# Hi-Hat.net
KiCad netlist of a schematic drawn in EAGLE
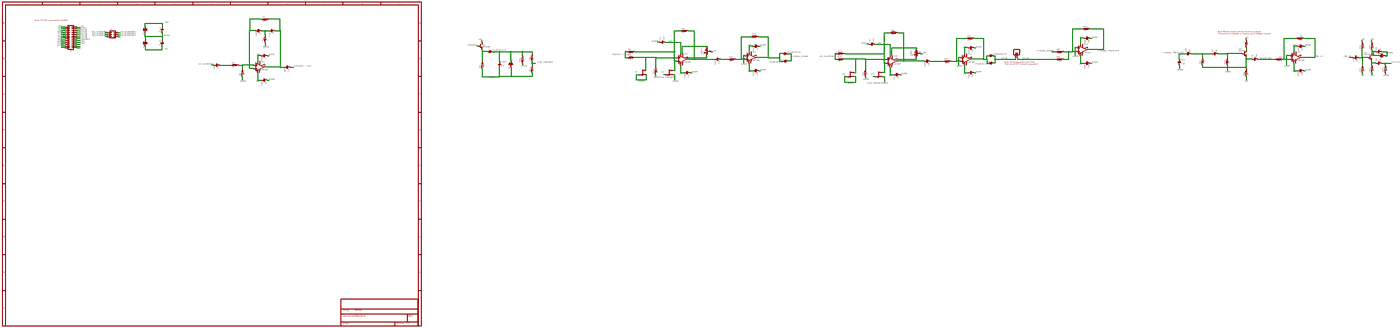
[diagram p0: schematic, sheet 1, overview]
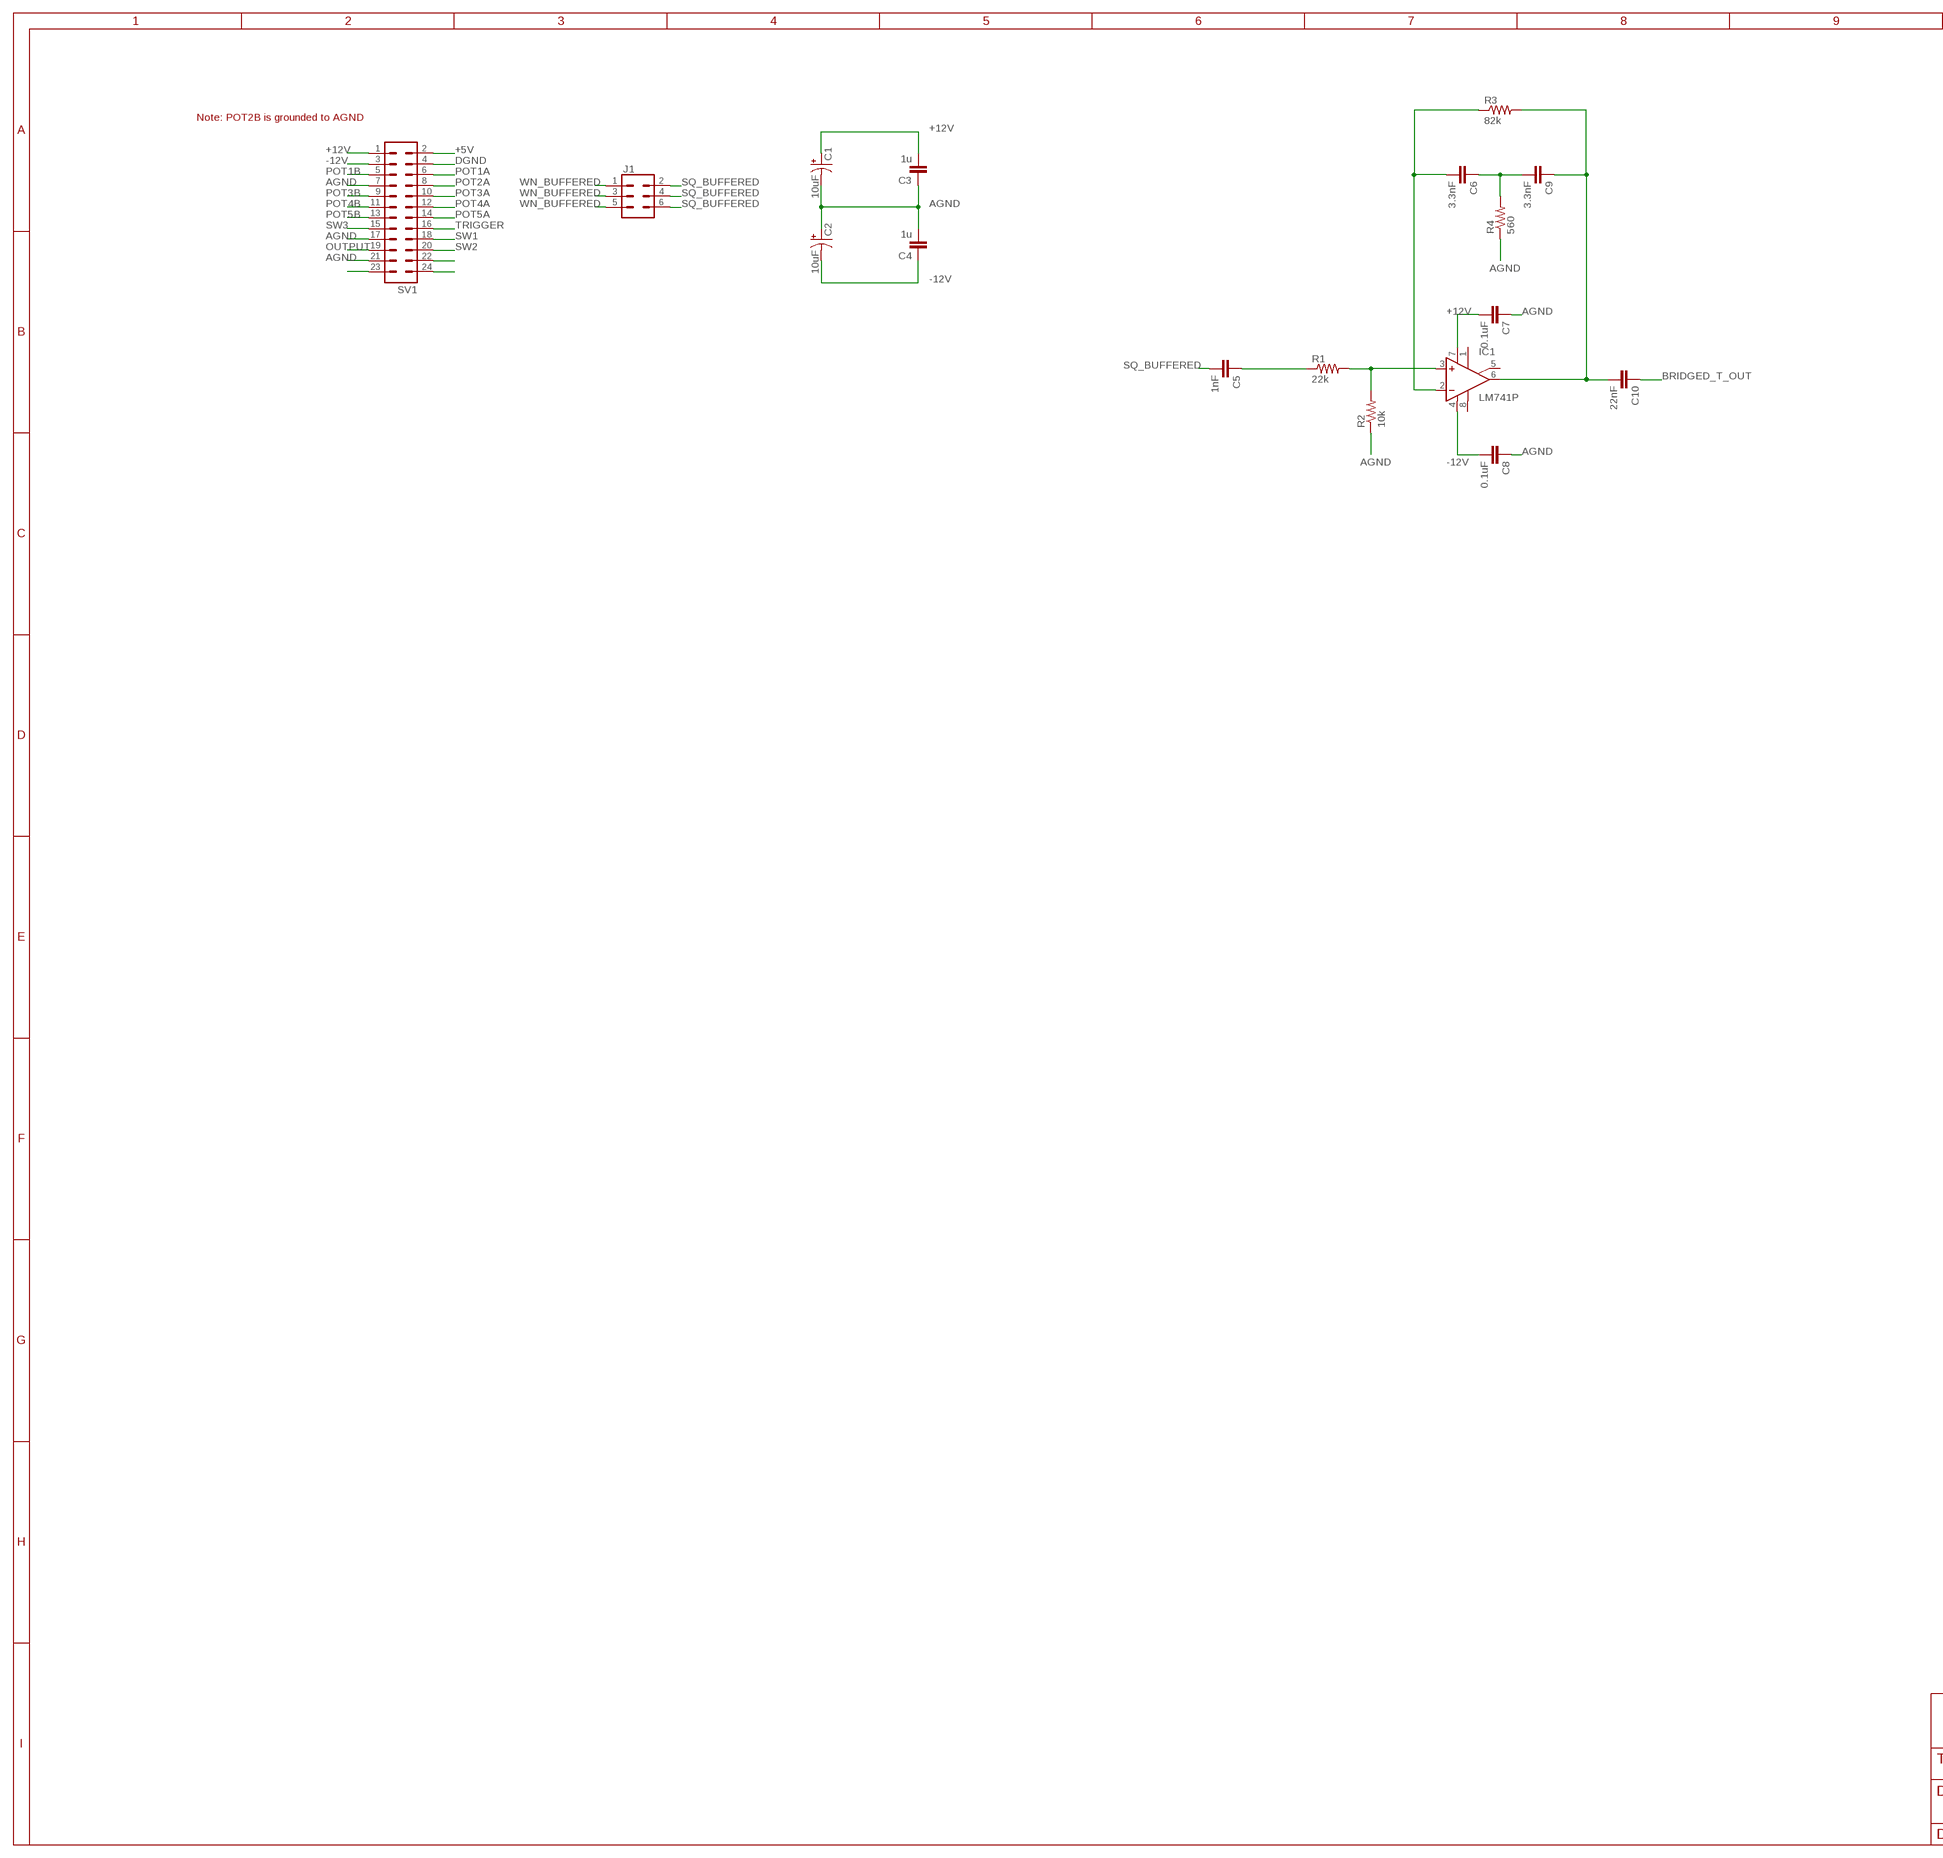
[diagram p1: schematic, sheet 1, part 1 of 4]
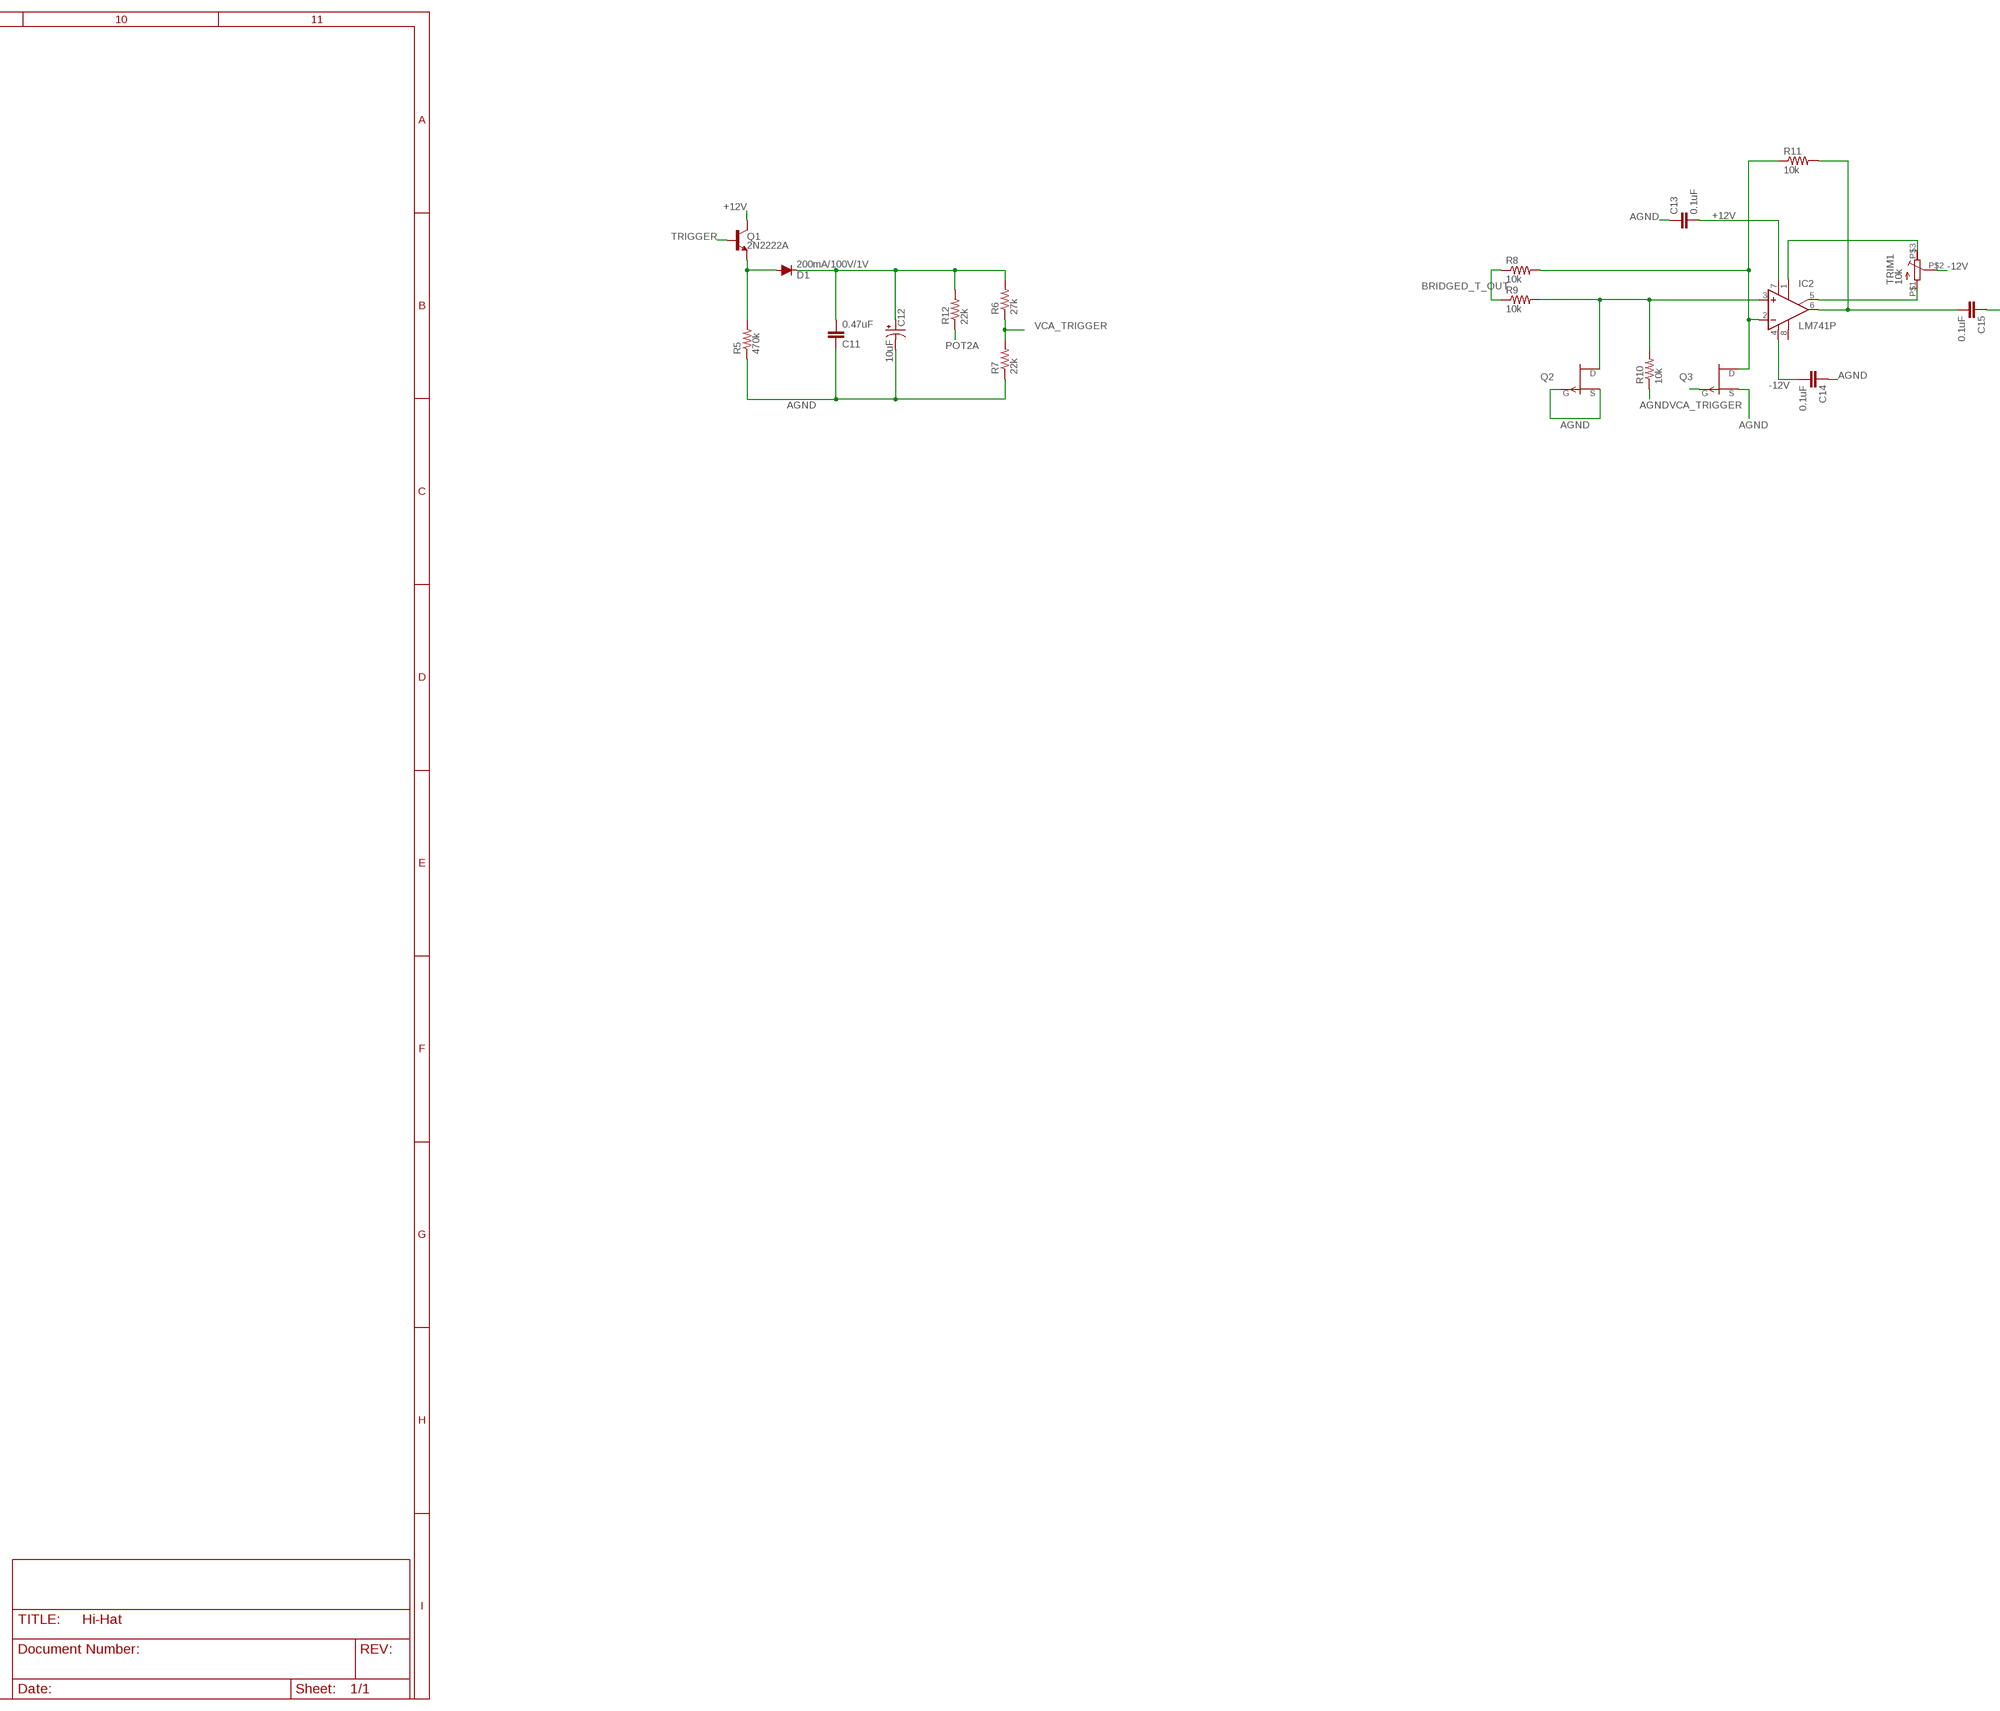
[diagram p2: schematic, sheet 1, part 2 of 4]
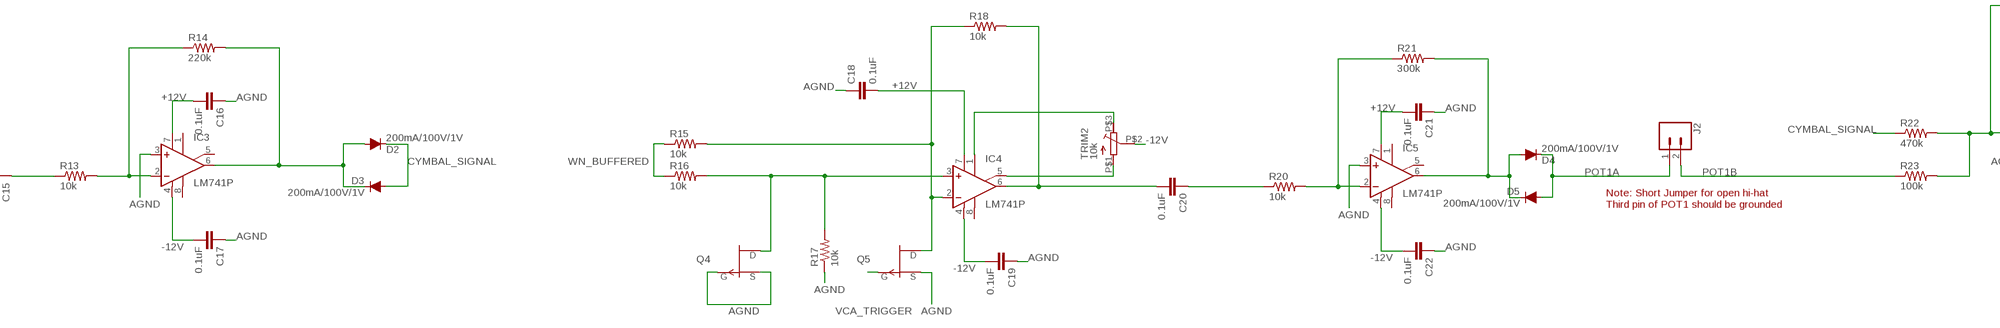
[diagram p3: schematic, sheet 1, part 3 of 4]
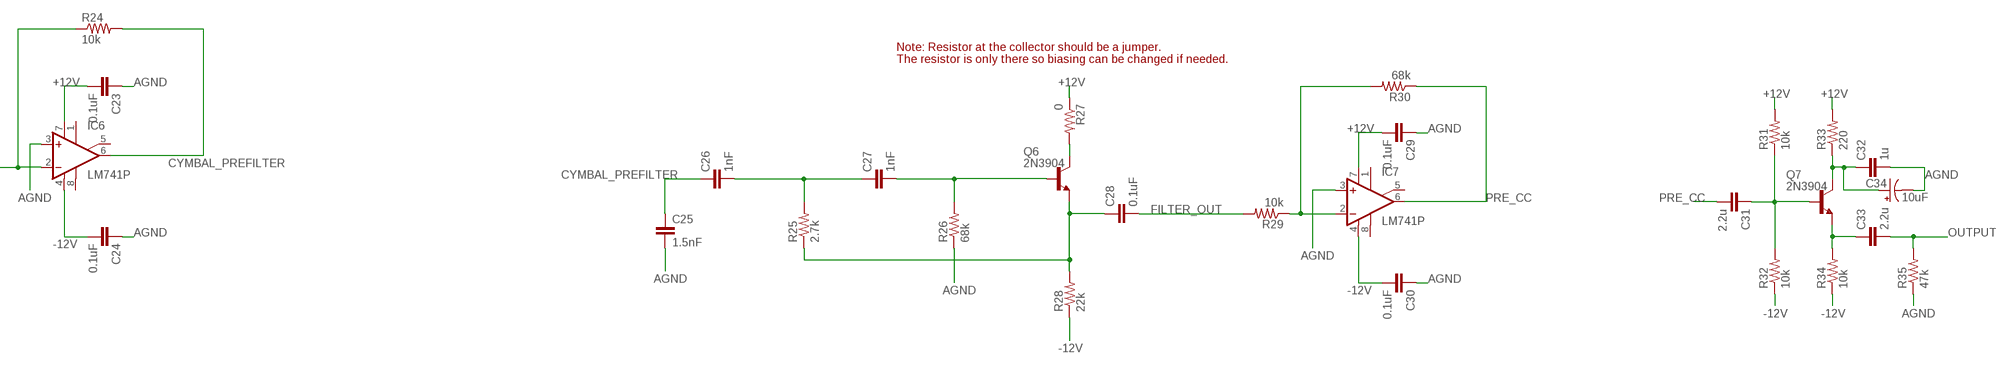
[diagram p4: schematic, sheet 1, part 4 of 4]

(export (version "E")
  (design (tool "Eeschema 10.0.6"))
  (components
    (comp (ref "C1")
      (value "10uF")
      (footprint "eagle-import:E2,5-6")
      (libsource (lib "eagle-import") (part "CPOL-USE2.5-6"))
    )
    (comp (ref "C2")
      (value "10uF")
      (footprint "eagle-import:E2,5-6")
      (libsource (lib "eagle-import") (part "CPOL-USE2.5-6"))
    )
    (comp (ref "C3")
      (value "1u")
      (footprint "eagle-import:C050-024X044")
      (libsource (lib "eagle-import") (part "C-EU050-024X044"))
    )
    (comp (ref "C4")
      (value "1u")
      (footprint "eagle-import:C050-024X044")
      (libsource (lib "eagle-import") (part "C-EU050-024X044"))
    )
    (comp (ref "C5")
      (value "1nF")
      (footprint "eagle-import:C050-024X044")
      (libsource (lib "eagle-import") (part "C-EU050-024X044"))
    )
    (comp (ref "C6")
      (value "3.3nF")
      (footprint "eagle-import:C050-024X044")
      (libsource (lib "eagle-import") (part "C-EU050-024X044"))
    )
    (comp (ref "C7")
      (value "0.1uF")
      (footprint "eagle-import:C050-024X044")
      (libsource (lib "eagle-import") (part "C-EU050-024X044"))
    )
    (comp (ref "C8")
      (value "0.1uF")
      (footprint "eagle-import:C050-024X044")
      (libsource (lib "eagle-import") (part "C-EU050-024X044"))
    )
    (comp (ref "C9")
      (value "3.3nF")
      (footprint "eagle-import:C050-024X044")
      (libsource (lib "eagle-import") (part "C-EU050-024X044"))
    )
    (comp (ref "C10")
      (value "22nF")
      (footprint "eagle-import:C050-024X044")
      (libsource (lib "eagle-import") (part "C-EU050-024X044"))
    )
    (comp (ref "C11")
      (value "0.47uF")
      (footprint "eagle-import:C050-024X044")
      (libsource (lib "eagle-import") (part "C-EU050-024X044"))
    )
    (comp (ref "C12")
      (value "10uF")
      (footprint "eagle-import:E2,5-6")
      (libsource (lib "eagle-import") (part "CPOL-USE2.5-6"))
    )
    (comp (ref "C13")
      (value "0.1uF")
      (footprint "eagle-import:C050-024X044")
      (libsource (lib "eagle-import") (part "C-EU050-024X044"))
    )
    (comp (ref "C14")
      (value "0.1uF")
      (footprint "eagle-import:C050-024X044")
      (libsource (lib "eagle-import") (part "C-EU050-024X044"))
    )
    (comp (ref "C15")
      (value "0.1uF")
      (footprint "eagle-import:C050-024X044")
      (libsource (lib "eagle-import") (part "C-EU050-024X044"))
    )
    (comp (ref "C16")
      (value "0.1uF")
      (footprint "eagle-import:C050-024X044")
      (libsource (lib "eagle-import") (part "C-EU050-024X044"))
    )
    (comp (ref "C17")
      (value "0.1uF")
      (footprint "eagle-import:C050-024X044")
      (libsource (lib "eagle-import") (part "C-EU050-024X044"))
    )
    (comp (ref "C18")
      (value "0.1uF")
      (footprint "eagle-import:C050-024X044")
      (libsource (lib "eagle-import") (part "C-EU050-024X044"))
    )
    (comp (ref "C19")
      (value "0.1uF")
      (footprint "eagle-import:C050-024X044")
      (libsource (lib "eagle-import") (part "C-EU050-024X044"))
    )
    (comp (ref "C20")
      (value "0.1uF")
      (footprint "eagle-import:C050-024X044")
      (libsource (lib "eagle-import") (part "C-EU050-024X044"))
    )
    (comp (ref "C21")
      (value "0.1uF")
      (footprint "eagle-import:C050-024X044")
      (libsource (lib "eagle-import") (part "C-EU050-024X044"))
    )
    (comp (ref "C22")
      (value "0.1uF")
      (footprint "eagle-import:C050-024X044")
      (libsource (lib "eagle-import") (part "C-EU050-024X044"))
    )
    (comp (ref "C23")
      (value "0.1uF")
      (footprint "eagle-import:C050-024X044")
      (libsource (lib "eagle-import") (part "C-EU050-024X044"))
    )
    (comp (ref "C24")
      (value "0.1uF")
      (footprint "eagle-import:C050-024X044")
      (libsource (lib "eagle-import") (part "C-EU050-024X044"))
    )
    (comp (ref "C25")
      (value "1.5nF")
      (footprint "eagle-import:C050-024X044")
      (libsource (lib "eagle-import") (part "C-EU050-024X044"))
    )
    (comp (ref "C26")
      (value "1nF")
      (footprint "eagle-import:C050-024X044")
      (libsource (lib "eagle-import") (part "C-EU050-024X044"))
    )
    (comp (ref "C27")
      (value "1nF")
      (footprint "eagle-import:C050-024X044")
      (libsource (lib "eagle-import") (part "C-EU050-024X044"))
    )
    (comp (ref "C28")
      (value "0.1uF")
      (footprint "eagle-import:C050-024X044")
      (libsource (lib "eagle-import") (part "C-EU050-024X044"))
    )
    (comp (ref "C29")
      (value "0.1uF")
      (footprint "eagle-import:C050-024X044")
      (libsource (lib "eagle-import") (part "C-EU050-024X044"))
    )
    (comp (ref "C30")
      (value "0.1uF")
      (footprint "eagle-import:C050-024X044")
      (libsource (lib "eagle-import") (part "C-EU050-024X044"))
    )
    (comp (ref "C31")
      (value "2.2u")
      (footprint "eagle-import:C050-024X044")
      (libsource (lib "eagle-import") (part "C-EU050-024X044"))
    )
    (comp (ref "C32")
      (value "1u")
      (footprint "eagle-import:C050-024X044")
      (libsource (lib "eagle-import") (part "C-EU050-024X044"))
    )
    (comp (ref "C33")
      (value "2.2u")
      (footprint "eagle-import:C050-024X044")
      (libsource (lib "eagle-import") (part "C-EU050-024X044"))
    )
    (comp (ref "C34")
      (value "10uF")
      (footprint "eagle-import:E2,5-6")
      (libsource (lib "eagle-import") (part "CPOL-USE2.5-6"))
    )
    (comp (ref "D1")
      (value "200mA/100V/1V")
      (footprint "eagle-import:DIODE-1N4148")
      (libsource (lib "eagle-import") (part "DIODE-1N4148"))
    )
    (comp (ref "D2")
      (value "200mA/100V/1V")
      (footprint "eagle-import:DIODE-1N4148")
      (libsource (lib "eagle-import") (part "DIODE-1N4148"))
    )
    (comp (ref "D3")
      (value "200mA/100V/1V")
      (footprint "eagle-import:DIODE-1N4148")
      (libsource (lib "eagle-import") (part "DIODE-1N4148"))
    )
    (comp (ref "D4")
      (value "200mA/100V/1V")
      (footprint "eagle-import:DIODE-1N4148")
      (libsource (lib "eagle-import") (part "DIODE-1N4148"))
    )
    (comp (ref "D5")
      (value "200mA/100V/1V")
      (footprint "eagle-import:DIODE-1N4148")
      (libsource (lib "eagle-import") (part "DIODE-1N4148"))
    )
    (comp (ref "IC1")
      (value "LM741P")
      (footprint "eagle-import:DIL08")
      (libsource (lib "eagle-import") (part "741PLM"))
    )
    (comp (ref "IC2")
      (value "LM741P")
      (footprint "eagle-import:DIL08")
      (libsource (lib "eagle-import") (part "741PLM"))
    )
    (comp (ref "IC3")
      (value "LM741P")
      (footprint "eagle-import:DIL08")
      (libsource (lib "eagle-import") (part "741PLM"))
    )
    (comp (ref "IC4")
      (value "LM741P")
      (footprint "eagle-import:DIL08")
      (libsource (lib "eagle-import") (part "741PLM"))
    )
    (comp (ref "IC5")
      (value "LM741P")
      (footprint "eagle-import:DIL08")
      (libsource (lib "eagle-import") (part "741PLM"))
    )
    (comp (ref "IC6")
      (value "LM741P")
      (footprint "eagle-import:DIL08")
      (libsource (lib "eagle-import") (part "741PLM"))
    )
    (comp (ref "IC7")
      (value "LM741P")
      (footprint "eagle-import:DIL08")
      (libsource (lib "eagle-import") (part "741PLM"))
    )
    (comp (ref "J1")
      (value "CONN_03X2NO_SILK")
      (footprint "eagle-import:2X3-NS")
      (libsource (lib "eagle-import") (part "CONN_03X2NO_SILK"))
    )
    (comp (ref "J2")
      (value "CONN_02")
      (footprint "eagle-import:1X02")
      (libsource (lib "eagle-import") (part "CONN_02"))
    )
    (comp (ref "Q1")
      (value "2N2222A")
      (footprint "eagle-import:TO-92")
      (libsource (lib "eagle-import") (part "TRANS_NPN-P2N2222A"))
    )
    (comp (ref "Q2")
      (value "J176")
      (footprint "eagle-import:TO-92")
      (libsource (lib "eagle-import") (part "J176"))
    )
    (comp (ref "Q3")
      (value "J176")
      (footprint "eagle-import:TO-92")
      (libsource (lib "eagle-import") (part "J176"))
    )
    (comp (ref "Q4")
      (value "J176")
      (footprint "eagle-import:TO-92")
      (libsource (lib "eagle-import") (part "J176"))
    )
    (comp (ref "Q5")
      (value "J176")
      (footprint "eagle-import:TO-92")
      (libsource (lib "eagle-import") (part "J176"))
    )
    (comp (ref "Q6")
      (value "2N3904")
      (footprint "eagle-import:TO92")
      (libsource (lib "eagle-import") (part "2N3904"))
    )
    (comp (ref "Q7")
      (value "2N3904")
      (footprint "eagle-import:TO92")
      (libsource (lib "eagle-import") (part "2N3904"))
    )
    (comp (ref "R1")
      (value "22k")
      (footprint "eagle-import:0207_7")
      (libsource (lib "eagle-import") (part "R-US_0207/7"))
    )
    (comp (ref "R2")
      (value "10k")
      (footprint "eagle-import:0207_7")
      (libsource (lib "eagle-import") (part "R-US_0207/7"))
    )
    (comp (ref "R3")
      (value "82k")
      (footprint "eagle-import:0207_7")
      (libsource (lib "eagle-import") (part "R-US_0207/7"))
    )
    (comp (ref "R4")
      (value "560")
      (footprint "eagle-import:0207_7")
      (libsource (lib "eagle-import") (part "R-US_0207/7"))
    )
    (comp (ref "R5")
      (value "470k")
      (footprint "eagle-import:0207_7")
      (libsource (lib "eagle-import") (part "R-US_0207/7"))
    )
    (comp (ref "R6")
      (value "27k")
      (footprint "eagle-import:0207_7")
      (libsource (lib "eagle-import") (part "R-US_0207/7"))
    )
    (comp (ref "R7")
      (value "22k")
      (footprint "eagle-import:0207_7")
      (libsource (lib "eagle-import") (part "R-US_0207/7"))
    )
    (comp (ref "R8")
      (value "10k")
      (footprint "eagle-import:0207_7")
      (libsource (lib "eagle-import") (part "R-US_0207/7"))
    )
    (comp (ref "R9")
      (value "10k")
      (footprint "eagle-import:0207_7")
      (libsource (lib "eagle-import") (part "R-US_0207/7"))
    )
    (comp (ref "R10")
      (value "10k")
      (footprint "eagle-import:0207_7")
      (libsource (lib "eagle-import") (part "R-US_0207/7"))
    )
    (comp (ref "R11")
      (value "10k")
      (footprint "eagle-import:0207_7")
      (libsource (lib "eagle-import") (part "R-US_0207/7"))
    )
    (comp (ref "R12")
      (value "22k")
      (footprint "eagle-import:0207_7")
      (libsource (lib "eagle-import") (part "R-US_0207/7"))
    )
    (comp (ref "R13")
      (value "10k")
      (footprint "eagle-import:0207_7")
      (libsource (lib "eagle-import") (part "R-US_0207/7"))
    )
    (comp (ref "R14")
      (value "220k")
      (footprint "eagle-import:0207_7")
      (libsource (lib "eagle-import") (part "R-US_0207/7"))
    )
    (comp (ref "R15")
      (value "10k")
      (footprint "eagle-import:0207_7")
      (libsource (lib "eagle-import") (part "R-US_0207/7"))
    )
    (comp (ref "R16")
      (value "10k")
      (footprint "eagle-import:0207_7")
      (libsource (lib "eagle-import") (part "R-US_0207/7"))
    )
    (comp (ref "R17")
      (value "10k")
      (footprint "eagle-import:0207_7")
      (libsource (lib "eagle-import") (part "R-US_0207/7"))
    )
    (comp (ref "R18")
      (value "10k")
      (footprint "eagle-import:0207_7")
      (libsource (lib "eagle-import") (part "R-US_0207/7"))
    )
    (comp (ref "R20")
      (value "10k")
      (footprint "eagle-import:0207_7")
      (libsource (lib "eagle-import") (part "R-US_0207/7"))
    )
    (comp (ref "R21")
      (value "300k")
      (footprint "eagle-import:0207_7")
      (libsource (lib "eagle-import") (part "R-US_0207/7"))
    )
    (comp (ref "R22")
      (value "470k")
      (footprint "eagle-import:0207_7")
      (libsource (lib "eagle-import") (part "R-US_0207/7"))
    )
    (comp (ref "R23")
      (value "100k")
      (footprint "eagle-import:0207_7")
      (libsource (lib "eagle-import") (part "R-US_0207/7"))
    )
    (comp (ref "R24")
      (value "10k")
      (footprint "eagle-import:0207_7")
      (libsource (lib "eagle-import") (part "R-US_0207/7"))
    )
    (comp (ref "R25")
      (value "2.7k")
      (footprint "eagle-import:0207_7")
      (libsource (lib "eagle-import") (part "R-US_0207/7"))
    )
    (comp (ref "R26")
      (value "68k")
      (footprint "eagle-import:0207_7")
      (libsource (lib "eagle-import") (part "R-US_0207/7"))
    )
    (comp (ref "R27")
      (value "0")
      (footprint "eagle-import:0207_7")
      (libsource (lib "eagle-import") (part "R-US_0207/7"))
    )
    (comp (ref "R28")
      (value "22k")
      (footprint "eagle-import:0207_7")
      (libsource (lib "eagle-import") (part "R-US_0207/7"))
    )
    (comp (ref "R29")
      (value "10k")
      (footprint "eagle-import:0207_7")
      (libsource (lib "eagle-import") (part "R-US_0207/7"))
    )
    (comp (ref "R30")
      (value "68k")
      (footprint "eagle-import:0207_7")
      (libsource (lib "eagle-import") (part "R-US_0207/7"))
    )
    (comp (ref "R31")
      (value "10k")
      (footprint "eagle-import:0207_7")
      (libsource (lib "eagle-import") (part "R-US_0207/7"))
    )
    (comp (ref "R32")
      (value "10k")
      (footprint "eagle-import:0207_7")
      (libsource (lib "eagle-import") (part "R-US_0207/7"))
    )
    (comp (ref "R33")
      (value "220")
      (footprint "eagle-import:0207_7")
      (libsource (lib "eagle-import") (part "R-US_0207/7"))
    )
    (comp (ref "R34")
      (value "10k")
      (footprint "eagle-import:0207_7")
      (libsource (lib "eagle-import") (part "R-US_0207/7"))
    )
    (comp (ref "R35")
      (value "47k")
      (footprint "eagle-import:0207_7")
      (libsource (lib "eagle-import") (part "R-US_0207/7"))
    )
    (comp (ref "SV1")
      (value "MA12-2")
      (footprint "eagle-import:MA12-2")
      (libsource (lib "eagle-import") (part "MA12-2"))
    )
    (comp (ref "TRIM1")
      (value "10k")
      (footprint "eagle-import:10K_TRIM")
      (libsource (lib "eagle-import") (part "10K_TRIMMER"))
    )
    (comp (ref "TRIM2")
      (value "10k")
      (footprint "eagle-import:10K_TRIM")
      (libsource (lib "eagle-import") (part "10K_TRIMMER"))
    )
  )
  (nets
    (net (code "1") (name "/+5V") (class "Default")
      (node (ref "SV1") (pin "2") (pinfunction "2_2") (pintype "passive"))
    )
    (net (code "2") (name "/+12V") (class "Default")
      (node (ref "C1") (pin "+") (pinfunction "+_+") (pintype "passive"))
      (node (ref "C13") (pin "2") (pinfunction "2_2") (pintype "passive"))
      (node (ref "C16") (pin "2") (pinfunction "2_2") (pintype "passive"))
      (node (ref "C18") (pin "2") (pinfunction "2_2") (pintype "passive"))
      (node (ref "C21") (pin "2") (pinfunction "2_2") (pintype "passive"))
      (node (ref "C23") (pin "2") (pinfunction "2_2") (pintype "passive"))
      (node (ref "C29") (pin "2") (pinfunction "2_2") (pintype "passive"))
      (node (ref "C3") (pin "2") (pinfunction "2_2") (pintype "passive"))
      (node (ref "C7") (pin "2") (pinfunction "2_2") (pintype "passive"))
      (node (ref "IC1") (pin "7") (pinfunction "V+_7") (pintype "power_in"))
      (node (ref "IC2") (pin "7") (pinfunction "V+_7") (pintype "power_in"))
      (node (ref "IC3") (pin "7") (pinfunction "V+_7") (pintype "power_in"))
      (node (ref "IC4") (pin "7") (pinfunction "V+_7") (pintype "power_in"))
      (node (ref "IC5") (pin "7") (pinfunction "V+_7") (pintype "power_in"))
      (node (ref "IC6") (pin "7") (pinfunction "V+_7") (pintype "power_in"))
      (node (ref "IC7") (pin "7") (pinfunction "V+_7") (pintype "power_in"))
      (node (ref "Q1") (pin "1") (pinfunction "C_1") (pintype "passive"))
      (node (ref "R27") (pin "1") (pinfunction "1_1") (pintype "passive"))
      (node (ref "R31") (pin "2") (pinfunction "2_2") (pintype "passive"))
      (node (ref "R33") (pin "2") (pinfunction "2_2") (pintype "passive"))
      (node (ref "SV1") (pin "1") (pinfunction "1_1") (pintype "passive"))
    )
    (net (code "3") (name "/-12V") (class "Default")
      (node (ref "C14") (pin "2") (pinfunction "2_2") (pintype "passive"))
      (node (ref "C17") (pin "2") (pinfunction "2_2") (pintype "passive"))
      (node (ref "C19") (pin "2") (pinfunction "2_2") (pintype "passive"))
      (node (ref "C2") (pin "-") (pinfunction "-_-") (pintype "passive"))
      (node (ref "C22") (pin "2") (pinfunction "2_2") (pintype "passive"))
      (node (ref "C24") (pin "2") (pinfunction "2_2") (pintype "passive"))
      (node (ref "C30") (pin "2") (pinfunction "2_2") (pintype "passive"))
      (node (ref "C4") (pin "1") (pinfunction "1_1") (pintype "passive"))
      (node (ref "C8") (pin "2") (pinfunction "2_2") (pintype "passive"))
      (node (ref "IC1") (pin "4") (pinfunction "V-_4") (pintype "power_in"))
      (node (ref "IC2") (pin "4") (pinfunction "V-_4") (pintype "power_in"))
      (node (ref "IC3") (pin "4") (pinfunction "V-_4") (pintype "power_in"))
      (node (ref "IC4") (pin "4") (pinfunction "V-_4") (pintype "power_in"))
      (node (ref "IC5") (pin "4") (pinfunction "V-_4") (pintype "power_in"))
      (node (ref "IC6") (pin "4") (pinfunction "V-_4") (pintype "power_in"))
      (node (ref "IC7") (pin "4") (pinfunction "V-_4") (pintype "power_in"))
      (node (ref "R28") (pin "1") (pinfunction "1_1") (pintype "passive"))
      (node (ref "R32") (pin "1") (pinfunction "1_1") (pintype "passive"))
      (node (ref "R34") (pin "1") (pinfunction "1_1") (pintype "passive"))
      (node (ref "SV1") (pin "3") (pinfunction "3_3") (pintype "passive"))
      (node (ref "TRIM1") (pin "P$2") (pinfunction "S_P$2") (pintype "passive"))
      (node (ref "TRIM2") (pin "P$2") (pinfunction "S_P$2") (pintype "passive"))
    )
    (net (code "4") (name "/AGND") (class "Default")
      (node (ref "C1") (pin "-") (pinfunction "-_-") (pintype "passive"))
      (node (ref "C11") (pin "1") (pinfunction "1_1") (pintype "passive"))
      (node (ref "C12") (pin "-") (pinfunction "-_-") (pintype "passive"))
      (node (ref "C13") (pin "1") (pinfunction "1_1") (pintype "passive"))
      (node (ref "C14") (pin "1") (pinfunction "1_1") (pintype "passive"))
      (node (ref "C16") (pin "1") (pinfunction "1_1") (pintype "passive"))
      (node (ref "C17") (pin "1") (pinfunction "1_1") (pintype "passive"))
      (node (ref "C18") (pin "1") (pinfunction "1_1") (pintype "passive"))
      (node (ref "C19") (pin "1") (pinfunction "1_1") (pintype "passive"))
      (node (ref "C2") (pin "+") (pinfunction "+_+") (pintype "passive"))
      (node (ref "C21") (pin "1") (pinfunction "1_1") (pintype "passive"))
      (node (ref "C22") (pin "1") (pinfunction "1_1") (pintype "passive"))
      (node (ref "C23") (pin "1") (pinfunction "1_1") (pintype "passive"))
      (node (ref "C24") (pin "1") (pinfunction "1_1") (pintype "passive"))
      (node (ref "C25") (pin "2") (pinfunction "2_2") (pintype "passive"))
      (node (ref "C29") (pin "1") (pinfunction "1_1") (pintype "passive"))
      (node (ref "C3") (pin "1") (pinfunction "1_1") (pintype "passive"))
      (node (ref "C30") (pin "1") (pinfunction "1_1") (pintype "passive"))
      (node (ref "C32") (pin "2") (pinfunction "2_2") (pintype "passive"))
      (node (ref "C34") (pin "-") (pinfunction "-_-") (pintype "passive"))
      (node (ref "C4") (pin "2") (pinfunction "2_2") (pintype "passive"))
      (node (ref "C7") (pin "1") (pinfunction "1_1") (pintype "passive"))
      (node (ref "C8") (pin "1") (pinfunction "1_1") (pintype "passive"))
      (node (ref "IC3") (pin "3") (pinfunction "+IN_3") (pintype "input"))
      (node (ref "IC5") (pin "3") (pinfunction "+IN_3") (pintype "input"))
      (node (ref "IC6") (pin "3") (pinfunction "+IN_3") (pintype "input"))
      (node (ref "IC7") (pin "3") (pinfunction "+IN_3") (pintype "input"))
      (node (ref "Q2") (pin "2") (pinfunction "G_2") (pintype "passive"))
      (node (ref "Q2") (pin "3") (pinfunction "S_3") (pintype "passive"))
      (node (ref "Q3") (pin "3") (pinfunction "S_3") (pintype "passive"))
      (node (ref "Q4") (pin "2") (pinfunction "G_2") (pintype "passive"))
      (node (ref "Q4") (pin "3") (pinfunction "S_3") (pintype "passive"))
      (node (ref "Q5") (pin "3") (pinfunction "S_3") (pintype "passive"))
      (node (ref "R10") (pin "1") (pinfunction "1_1") (pintype "passive"))
      (node (ref "R17") (pin "1") (pinfunction "1_1") (pintype "passive"))
      (node (ref "R2") (pin "1") (pinfunction "1_1") (pintype "passive"))
      (node (ref "R26") (pin "1") (pinfunction "1_1") (pintype "passive"))
      (node (ref "R35") (pin "1") (pinfunction "1_1") (pintype "passive"))
      (node (ref "R4") (pin "1") (pinfunction "1_1") (pintype "passive"))
      (node (ref "R5") (pin "1") (pinfunction "1_1") (pintype "passive"))
      (node (ref "R7") (pin "1") (pinfunction "1_1") (pintype "passive"))
      (node (ref "SV1") (pin "17") (pinfunction "17_17") (pintype "passive"))
      (node (ref "SV1") (pin "21") (pinfunction "21_21") (pintype "passive"))
      (node (ref "SV1") (pin "7") (pinfunction "7_7") (pintype "passive"))
    )
    (net (code "5") (name "/BRIDGED_T_OUT") (class "Default")
      (node (ref "C10") (pin "1") (pinfunction "1_1") (pintype "passive"))
      (node (ref "R8") (pin "1") (pinfunction "1_1") (pintype "passive"))
      (node (ref "R9") (pin "1") (pinfunction "1_1") (pintype "passive"))
    )
    (net (code "6") (name "/CYMBAL_PREFILTER") (class "Default")
      (node (ref "C25") (pin "1") (pinfunction "1_1") (pintype "passive"))
      (node (ref "C26") (pin "1") (pinfunction "1_1") (pintype "passive"))
      (node (ref "IC6") (pin "6") (pinfunction "OUT_6") (pintype "output"))
      (node (ref "R24") (pin "2") (pinfunction "2_2") (pintype "passive"))
    )
    (net (code "7") (name "/CYMBAL_SIGNAL") (class "Default")
      (node (ref "D2") (pin "C") (pinfunction "C_C") (pintype "passive"))
      (node (ref "D3") (pin "A") (pinfunction "A_A") (pintype "passive"))
      (node (ref "R22") (pin "1") (pinfunction "1_1") (pintype "passive"))
    )
    (net (code "8") (name "/DGND") (class "Default")
      (node (ref "SV1") (pin "4") (pinfunction "4_4") (pintype "passive"))
    )
    (net (code "9") (name "/FILTER_OUT") (class "Default")
      (node (ref "C28") (pin "2") (pinfunction "2_2") (pintype "passive"))
      (node (ref "R29") (pin "2") (pinfunction "2_2") (pintype "passive"))
    )
    (net (code "10") (name "/OUTPUT") (class "Default")
      (node (ref "C33") (pin "2") (pinfunction "2_2") (pintype "passive"))
      (node (ref "R35") (pin "2") (pinfunction "2_2") (pintype "passive"))
      (node (ref "SV1") (pin "19") (pinfunction "19_19") (pintype "passive"))
    )
    (net (code "11") (name "/POT1A") (class "Default")
      (node (ref "D4") (pin "C") (pinfunction "C_C") (pintype "passive"))
      (node (ref "D5") (pin "A") (pinfunction "A_A") (pintype "passive"))
      (node (ref "J2") (pin "1") (pinfunction "1_1") (pintype "passive"))
      (node (ref "SV1") (pin "6") (pinfunction "6_6") (pintype "passive"))
    )
    (net (code "12") (name "/POT1B") (class "Default")
      (node (ref "J2") (pin "2") (pinfunction "2_2") (pintype "passive"))
      (node (ref "R23") (pin "1") (pinfunction "1_1") (pintype "passive"))
      (node (ref "SV1") (pin "5") (pinfunction "5_5") (pintype "passive"))
    )
    (net (code "13") (name "/POT2A") (class "Default")
      (node (ref "R12") (pin "1") (pinfunction "1_1") (pintype "passive"))
      (node (ref "SV1") (pin "8") (pinfunction "8_8") (pintype "passive"))
    )
    (net (code "14") (name "/POT3A") (class "Default")
      (node (ref "SV1") (pin "10") (pinfunction "10_10") (pintype "passive"))
    )
    (net (code "15") (name "/POT3B") (class "Default")
      (node (ref "SV1") (pin "9") (pinfunction "9_9") (pintype "passive"))
    )
    (net (code "16") (name "/POT4A") (class "Default")
      (node (ref "SV1") (pin "12") (pinfunction "12_12") (pintype "passive"))
    )
    (net (code "17") (name "/POT4B") (class "Default")
      (node (ref "SV1") (pin "11") (pinfunction "11_11") (pintype "passive"))
    )
    (net (code "18") (name "/POT5A") (class "Default")
      (node (ref "SV1") (pin "14") (pinfunction "14_14") (pintype "passive"))
    )
    (net (code "19") (name "/POT5B") (class "Default")
      (node (ref "SV1") (pin "13") (pinfunction "13_13") (pintype "passive"))
    )
    (net (code "20") (name "/PRE_CC") (class "Default")
      (node (ref "C31") (pin "2") (pinfunction "2_2") (pintype "passive"))
      (node (ref "IC7") (pin "6") (pinfunction "OUT_6") (pintype "output"))
      (node (ref "R30") (pin "1") (pinfunction "1_1") (pintype "passive"))
    )
    (net (code "21") (name "/SQ_BUFFERED") (class "Default")
      (node (ref "C5") (pin "2") (pinfunction "2_2") (pintype "passive"))
      (node (ref "J1") (pin "2") (pinfunction "2_2") (pintype "bidirectional"))
      (node (ref "J1") (pin "4") (pinfunction "4_4") (pintype "bidirectional"))
      (node (ref "J1") (pin "6") (pinfunction "6_6") (pintype "bidirectional"))
    )
    (net (code "22") (name "/SW1") (class "Default")
      (node (ref "SV1") (pin "18") (pinfunction "18_18") (pintype "passive"))
    )
    (net (code "23") (name "/SW2") (class "Default")
      (node (ref "SV1") (pin "20") (pinfunction "20_20") (pintype "passive"))
    )
    (net (code "24") (name "/SW3") (class "Default")
      (node (ref "SV1") (pin "15") (pinfunction "15_15") (pintype "passive"))
    )
    (net (code "25") (name "/TRIGGER") (class "Default")
      (node (ref "Q1") (pin "2") (pinfunction "B_2") (pintype "passive"))
      (node (ref "SV1") (pin "16") (pinfunction "16_16") (pintype "passive"))
    )
    (net (code "26") (name "/VCA_TRIGGER") (class "Default")
      (node (ref "Q3") (pin "2") (pinfunction "G_2") (pintype "passive"))
      (node (ref "Q5") (pin "2") (pinfunction "G_2") (pintype "passive"))
      (node (ref "R6") (pin "1") (pinfunction "1_1") (pintype "passive"))
      (node (ref "R7") (pin "2") (pinfunction "2_2") (pintype "passive"))
    )
    (net (code "27") (name "/WN_BUFFERED") (class "Default")
      (node (ref "J1") (pin "1") (pinfunction "1_1") (pintype "bidirectional"))
      (node (ref "J1") (pin "3") (pinfunction "3_3") (pintype "bidirectional"))
      (node (ref "J1") (pin "5") (pinfunction "5_5") (pintype "bidirectional"))
      (node (ref "R15") (pin "1") (pinfunction "1_1") (pintype "passive"))
      (node (ref "R16") (pin "1") (pinfunction "1_1") (pintype "passive"))
    )
    (net (code "28") (name "Net-(C5-Pad1)") (class "Default")
      (node (ref "C5") (pin "1") (pinfunction "1_1") (pintype "passive"))
      (node (ref "R1") (pin "1") (pinfunction "1_1") (pintype "passive"))
    )
    (net (code "29") (name "Net-(C6-Pad1)") (class "Default")
      (node (ref "C6") (pin "1") (pinfunction "1_1") (pintype "passive"))
      (node (ref "C9") (pin "2") (pinfunction "2_2") (pintype "passive"))
      (node (ref "R4") (pin "2") (pinfunction "2_2") (pintype "passive"))
    )
    (net (code "30") (name "Net-(C11-Pad2)") (class "Default")
      (node (ref "C11") (pin "2") (pinfunction "2_2") (pintype "passive"))
      (node (ref "C12") (pin "+") (pinfunction "+_+") (pintype "passive"))
      (node (ref "D1") (pin "C") (pinfunction "C_C") (pintype "passive"))
      (node (ref "R12") (pin "2") (pinfunction "2_2") (pintype "passive"))
      (node (ref "R6") (pin "2") (pinfunction "2_2") (pintype "passive"))
    )
    (net (code "31") (name "Net-(C15-Pad1)") (class "Default")
      (node (ref "C15") (pin "1") (pinfunction "1_1") (pintype "passive"))
      (node (ref "R13") (pin "1") (pinfunction "1_1") (pintype "passive"))
    )
    (net (code "32") (name "Net-(C20-Pad1)") (class "Default")
      (node (ref "C20") (pin "1") (pinfunction "1_1") (pintype "passive"))
      (node (ref "R20") (pin "1") (pinfunction "1_1") (pintype "passive"))
    )
    (net (code "33") (name "Net-(C26-Pad2)") (class "Default")
      (node (ref "C26") (pin "2") (pinfunction "2_2") (pintype "passive"))
      (node (ref "C27") (pin "1") (pinfunction "1_1") (pintype "passive"))
      (node (ref "R25") (pin "2") (pinfunction "2_2") (pintype "passive"))
    )
    (net (code "34") (name "Net-(IC1-+IN)") (class "Default")
      (node (ref "IC1") (pin "3") (pinfunction "+IN_3") (pintype "input"))
      (node (ref "R1") (pin "2") (pinfunction "2_2") (pintype "passive"))
      (node (ref "R2") (pin "2") (pinfunction "2_2") (pintype "passive"))
    )
    (net (code "35") (name "Net-(IC1--IN)") (class "Default")
      (node (ref "C6") (pin "2") (pinfunction "2_2") (pintype "passive"))
      (node (ref "IC1") (pin "2") (pinfunction "-IN_2") (pintype "input"))
      (node (ref "R3") (pin "1") (pinfunction "1_1") (pintype "passive"))
    )
    (net (code "36") (name "Net-(IC1-OUT)") (class "Default")
      (node (ref "C10") (pin "2") (pinfunction "2_2") (pintype "passive"))
      (node (ref "C9") (pin "1") (pinfunction "1_1") (pintype "passive"))
      (node (ref "IC1") (pin "6") (pinfunction "OUT_6") (pintype "output"))
      (node (ref "R3") (pin "2") (pinfunction "2_2") (pintype "passive"))
    )
    (net (code "37") (name "Net-(IC2-+IN)") (class "Default")
      (node (ref "IC2") (pin "3") (pinfunction "+IN_3") (pintype "input"))
      (node (ref "Q2") (pin "1") (pinfunction "D_1") (pintype "passive"))
      (node (ref "R10") (pin "2") (pinfunction "2_2") (pintype "passive"))
      (node (ref "R9") (pin "2") (pinfunction "2_2") (pintype "passive"))
    )
    (net (code "38") (name "Net-(IC2--IN)") (class "Default")
      (node (ref "IC2") (pin "2") (pinfunction "-IN_2") (pintype "input"))
      (node (ref "Q3") (pin "1") (pinfunction "D_1") (pintype "passive"))
      (node (ref "R11") (pin "1") (pinfunction "1_1") (pintype "passive"))
      (node (ref "R8") (pin "2") (pinfunction "2_2") (pintype "passive"))
    )
    (net (code "39") (name "Net-(IC2-ON1)") (class "Default")
      (node (ref "IC2") (pin "1") (pinfunction "ON1_1") (pintype "passive"))
      (node (ref "TRIM1") (pin "P$3") (pinfunction "E_P$3") (pintype "passive"))
    )
    (net (code "40") (name "Net-(IC2-ON2)") (class "Default")
      (node (ref "IC2") (pin "5") (pinfunction "ON2_5") (pintype "passive"))
      (node (ref "TRIM1") (pin "P$1") (pinfunction "A_P$1") (pintype "passive"))
    )
    (net (code "41") (name "Net-(IC2-OUT)") (class "Default")
      (node (ref "C15") (pin "2") (pinfunction "2_2") (pintype "passive"))
      (node (ref "IC2") (pin "6") (pinfunction "OUT_6") (pintype "output"))
      (node (ref "R11") (pin "2") (pinfunction "2_2") (pintype "passive"))
    )
    (net (code "42") (name "Net-(IC3--IN)") (class "Default")
      (node (ref "IC3") (pin "2") (pinfunction "-IN_2") (pintype "input"))
      (node (ref "R13") (pin "2") (pinfunction "2_2") (pintype "passive"))
      (node (ref "R14") (pin "1") (pinfunction "1_1") (pintype "passive"))
    )
    (net (code "43") (name "Net-(IC3-OUT)") (class "Default")
      (node (ref "D2") (pin "A") (pinfunction "A_A") (pintype "passive"))
      (node (ref "D3") (pin "C") (pinfunction "C_C") (pintype "passive"))
      (node (ref "IC3") (pin "6") (pinfunction "OUT_6") (pintype "output"))
      (node (ref "R14") (pin "2") (pinfunction "2_2") (pintype "passive"))
    )
    (net (code "44") (name "Net-(IC4-+IN)") (class "Default")
      (node (ref "IC4") (pin "3") (pinfunction "+IN_3") (pintype "input"))
      (node (ref "Q4") (pin "1") (pinfunction "D_1") (pintype "passive"))
      (node (ref "R16") (pin "2") (pinfunction "2_2") (pintype "passive"))
      (node (ref "R17") (pin "2") (pinfunction "2_2") (pintype "passive"))
    )
    (net (code "45") (name "Net-(IC4--IN)") (class "Default")
      (node (ref "IC4") (pin "2") (pinfunction "-IN_2") (pintype "input"))
      (node (ref "Q5") (pin "1") (pinfunction "D_1") (pintype "passive"))
      (node (ref "R15") (pin "2") (pinfunction "2_2") (pintype "passive"))
      (node (ref "R18") (pin "1") (pinfunction "1_1") (pintype "passive"))
    )
    (net (code "46") (name "Net-(IC4-ON1)") (class "Default")
      (node (ref "IC4") (pin "1") (pinfunction "ON1_1") (pintype "passive"))
      (node (ref "TRIM2") (pin "P$3") (pinfunction "E_P$3") (pintype "passive"))
    )
    (net (code "47") (name "Net-(IC4-ON2)") (class "Default")
      (node (ref "IC4") (pin "5") (pinfunction "ON2_5") (pintype "passive"))
      (node (ref "TRIM2") (pin "P$1") (pinfunction "A_P$1") (pintype "passive"))
    )
    (net (code "48") (name "Net-(IC4-OUT)") (class "Default")
      (node (ref "C20") (pin "2") (pinfunction "2_2") (pintype "passive"))
      (node (ref "IC4") (pin "6") (pinfunction "OUT_6") (pintype "output"))
      (node (ref "R18") (pin "2") (pinfunction "2_2") (pintype "passive"))
    )
    (net (code "49") (name "Net-(IC5--IN)") (class "Default")
      (node (ref "IC5") (pin "2") (pinfunction "-IN_2") (pintype "input"))
      (node (ref "R20") (pin "2") (pinfunction "2_2") (pintype "passive"))
      (node (ref "R21") (pin "1") (pinfunction "1_1") (pintype "passive"))
    )
    (net (code "50") (name "Net-(IC5-OUT)") (class "Default")
      (node (ref "D4") (pin "A") (pinfunction "A_A") (pintype "passive"))
      (node (ref "D5") (pin "C") (pinfunction "C_C") (pintype "passive"))
      (node (ref "IC5") (pin "6") (pinfunction "OUT_6") (pintype "output"))
      (node (ref "R21") (pin "2") (pinfunction "2_2") (pintype "passive"))
    )
    (net (code "51") (name "Net-(IC6--IN)") (class "Default")
      (node (ref "IC6") (pin "2") (pinfunction "-IN_2") (pintype "input"))
      (node (ref "R22") (pin "2") (pinfunction "2_2") (pintype "passive"))
      (node (ref "R23") (pin "2") (pinfunction "2_2") (pintype "passive"))
      (node (ref "R24") (pin "1") (pinfunction "1_1") (pintype "passive"))
    )
    (net (code "52") (name "Net-(IC7--IN)") (class "Default")
      (node (ref "IC7") (pin "2") (pinfunction "-IN_2") (pintype "input"))
      (node (ref "R29") (pin "1") (pinfunction "1_1") (pintype "passive"))
      (node (ref "R30") (pin "2") (pinfunction "2_2") (pintype "passive"))
    )
    (net (code "53") (name "Net-(Q1-E)") (class "Default")
      (node (ref "D1") (pin "A") (pinfunction "A_A") (pintype "passive"))
      (node (ref "Q1") (pin "3") (pinfunction "E_3") (pintype "passive"))
      (node (ref "R5") (pin "2") (pinfunction "2_2") (pintype "passive"))
    )
    (net (code "54") (name "Net-(Q6-B)") (class "Default")
      (node (ref "C27") (pin "2") (pinfunction "2_2") (pintype "passive"))
      (node (ref "Q6") (pin "2") (pinfunction "B_2") (pintype "passive"))
      (node (ref "R26") (pin "2") (pinfunction "2_2") (pintype "passive"))
    )
    (net (code "55") (name "Net-(Q6-C)") (class "Default")
      (node (ref "Q6") (pin "1") (pinfunction "C_1") (pintype "passive"))
      (node (ref "R27") (pin "2") (pinfunction "2_2") (pintype "passive"))
    )
    (net (code "56") (name "Net-(Q6-E)") (class "Default")
      (node (ref "C28") (pin "1") (pinfunction "1_1") (pintype "passive"))
      (node (ref "Q6") (pin "3") (pinfunction "E_3") (pintype "passive"))
      (node (ref "R25") (pin "1") (pinfunction "1_1") (pintype "passive"))
      (node (ref "R28") (pin "2") (pinfunction "2_2") (pintype "passive"))
    )
    (net (code "57") (name "Net-(Q7-B)") (class "Default")
      (node (ref "C31") (pin "1") (pinfunction "1_1") (pintype "passive"))
      (node (ref "Q7") (pin "2") (pinfunction "B_2") (pintype "passive"))
      (node (ref "R31") (pin "1") (pinfunction "1_1") (pintype "passive"))
      (node (ref "R32") (pin "2") (pinfunction "2_2") (pintype "passive"))
    )
    (net (code "58") (name "Net-(Q7-C)") (class "Default")
      (node (ref "C32") (pin "1") (pinfunction "1_1") (pintype "passive"))
      (node (ref "C34") (pin "+") (pinfunction "+_+") (pintype "passive"))
      (node (ref "Q7") (pin "1") (pinfunction "C_1") (pintype "passive"))
      (node (ref "R33") (pin "1") (pinfunction "1_1") (pintype "passive"))
    )
    (net (code "59") (name "Net-(Q7-E)") (class "Default")
      (node (ref "C33") (pin "1") (pinfunction "1_1") (pintype "passive"))
      (node (ref "Q7") (pin "3") (pinfunction "E_3") (pintype "passive"))
      (node (ref "R34") (pin "2") (pinfunction "2_2") (pintype "passive"))
    )
    (net (code "60") (name "unconnected-(IC1-ON1-Pad1)") (class "Default")
      (node (ref "IC1") (pin "1") (pinfunction "ON1_1") (pintype "passive"))
    )
    (net (code "61") (name "unconnected-(IC1-ON2-Pad5)") (class "Default")
      (node (ref "IC1") (pin "5") (pinfunction "ON2_5") (pintype "passive"))
    )
    (net (code "62") (name "unconnected-(IC1-OPT-Pad8)") (class "Default")
      (node (ref "IC1") (pin "8") (pinfunction "OPT_8") (pintype "passive"))
    )
    (net (code "63") (name "unconnected-(IC2-OPT-Pad8)") (class "Default")
      (node (ref "IC2") (pin "8") (pinfunction "OPT_8") (pintype "passive"))
    )
    (net (code "64") (name "unconnected-(IC3-ON1-Pad1)") (class "Default")
      (node (ref "IC3") (pin "1") (pinfunction "ON1_1") (pintype "passive"))
    )
    (net (code "65") (name "unconnected-(IC3-ON2-Pad5)") (class "Default")
      (node (ref "IC3") (pin "5") (pinfunction "ON2_5") (pintype "passive"))
    )
    (net (code "66") (name "unconnected-(IC3-OPT-Pad8)") (class "Default")
      (node (ref "IC3") (pin "8") (pinfunction "OPT_8") (pintype "passive"))
    )
    (net (code "67") (name "unconnected-(IC4-OPT-Pad8)") (class "Default")
      (node (ref "IC4") (pin "8") (pinfunction "OPT_8") (pintype "passive"))
    )
    (net (code "68") (name "unconnected-(IC5-ON1-Pad1)") (class "Default")
      (node (ref "IC5") (pin "1") (pinfunction "ON1_1") (pintype "passive"))
    )
    (net (code "69") (name "unconnected-(IC5-ON2-Pad5)") (class "Default")
      (node (ref "IC5") (pin "5") (pinfunction "ON2_5") (pintype "passive"))
    )
    (net (code "70") (name "unconnected-(IC5-OPT-Pad8)") (class "Default")
      (node (ref "IC5") (pin "8") (pinfunction "OPT_8") (pintype "passive"))
    )
    (net (code "71") (name "unconnected-(IC6-ON1-Pad1)") (class "Default")
      (node (ref "IC6") (pin "1") (pinfunction "ON1_1") (pintype "passive"))
    )
    (net (code "72") (name "unconnected-(IC6-ON2-Pad5)") (class "Default")
      (node (ref "IC6") (pin "5") (pinfunction "ON2_5") (pintype "passive"))
    )
    (net (code "73") (name "unconnected-(IC6-OPT-Pad8)") (class "Default")
      (node (ref "IC6") (pin "8") (pinfunction "OPT_8") (pintype "passive"))
    )
    (net (code "74") (name "unconnected-(IC7-ON1-Pad1)") (class "Default")
      (node (ref "IC7") (pin "1") (pinfunction "ON1_1") (pintype "passive"))
    )
    (net (code "75") (name "unconnected-(IC7-ON2-Pad5)") (class "Default")
      (node (ref "IC7") (pin "5") (pinfunction "ON2_5") (pintype "passive"))
    )
    (net (code "76") (name "unconnected-(IC7-OPT-Pad8)") (class "Default")
      (node (ref "IC7") (pin "8") (pinfunction "OPT_8") (pintype "passive"))
    )
    (net (code "77") (name "unconnected-(SV1-Pad22)") (class "Default")
      (node (ref "SV1") (pin "22") (pinfunction "22_22") (pintype "passive"))
    )
    (net (code "78") (name "unconnected-(SV1-Pad23)") (class "Default")
      (node (ref "SV1") (pin "23") (pinfunction "23_23") (pintype "passive"))
    )
    (net (code "79") (name "unconnected-(SV1-Pad24)") (class "Default")
      (node (ref "SV1") (pin "24") (pinfunction "24_24") (pintype "passive"))
    )
  )
)
